# 05_Power.net
KiCad netlist of a schematic drawn in Altium Designer
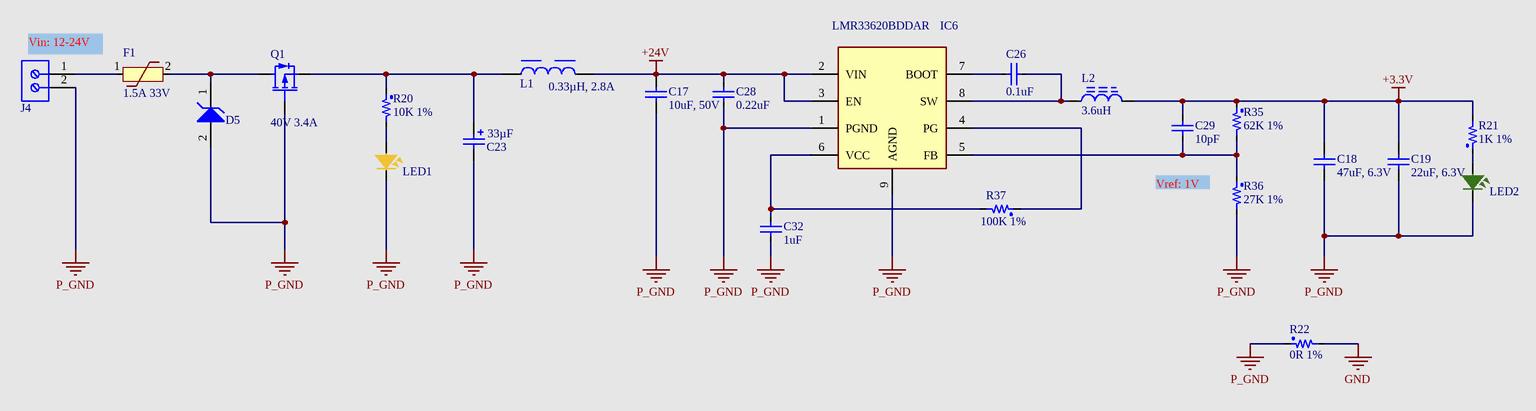
[diagram p0: 05_Power.SchDoc]

(export (version "E")
  (design (tool "Eeschema 10.0.6"))
  (components
    (comp (ref "C17")
      (value "10uF, 50V")
      (footprint "WCAP-CSGP_1210_H=2.5mm")
      (description "WCAP-CSGP Multilayer Ceramic Chip Capacitor, General Purpose, size 1210, X7R, 10uF, 50V")
      (fields (field (name "MFR PART NUMBER") "885012209073") (field (name "MFR") "Wurth Elektronik"))
      (libsource (lib "Altium_WCAP-CSGP (rev21a)") (part "885012209073"))
    )
    (comp (ref "C18")
      (value "47uF, 6.3V")
      (footprint "WCAP-CSGP_1206_H=1.6mm")
      (description "WCAP-CSGP Multilayer Ceramic Chip Capacitor, General Purpose, size 1206, X5R, 47uF, 6.3V")
      (fields (field (name "MFR PART NUMBER") "885012108004") (field (name "MFR") "Wurth Elektronik"))
      (libsource (lib "Altium_WCAP-CSGP (rev21a)") (part "885012108004"))
    )
    (comp (ref "C19")
      (value "22uF, 6.3V")
      (footprint "WCAP-CSGP_1206_H=1.6mm")
      (description "WCAP-CSGP Multilayer Ceramic Chip Capacitor, General Purpose, size 1206, X5R, 22uF, 6.3V")
      (fields (field (name "MFR PART NUMBER") "885012108003") (field (name "MFR") "Wurth Elektronik"))
      (libsource (lib "Altium_WCAP-CSGP (rev21a)") (part "885012108003"))
    )
    (comp (ref "C23")
      (value "33µF")
      (footprint "WCAP-PSLP_D5H5.8")
      (description "WCAP-PSLP Aluminum Polymer Capacitor, V-Chip SMT, D5 x H5.8mm, 33µF, 16V")
      (fields (field (name "MFR PART NUMBER") "875105359004") (field (name "MFR") "Wurth Elektronik"))
      (libsource (lib "Altium_WCAP-PSLP (rev22b)") (part "875105359004"))
    )
    (comp (ref "C26")
      (value "0.1uF")
      (footprint "Capacitor:C0603 (1608 metric)")
      (description "Multilayer Ceramic Capacitors MLCC - SMD/SMT 0.1uF 50V X7R +/-10% 0603")
      (fields (field (name "MFR PART NUMBER") "CC0603KRX7R9BB104") (field (name "MFR") "Yageo"))
      (libsource (lib "CeramicCapacitor") (part "CC0603KRX7R9BB104"))
    )
    (comp (ref "C28")
      (value "0.22uF")
      (footprint "Capacitor:C0805 (2012 METRIC)")
      (description "Multilayer Ceramic Capacitors MLCC - SMD/SMT 0805 50VDC 0.22uF 10% X7R")
      (fields (field (name "MFR PART NUMBER") "UMK212B7224KG-T") (field (name "MFR") "Taiyo Yuden"))
      (libsource (lib "CeramicCapacitor") (part "UMK212B7224KG-T"))
    )
    (comp (ref "C29")
      (value "10pF")
      (footprint "Capacitor:C0603 (1608 metric)")
      (description "Multilayer Ceramic Capacitors MLCC - SMD/SMT 10pF 250V C0G +/-5% 0603")
      (fields (field (name "MFR PART NUMBER") "CC0603JRNPO9BN100") (field (name "MFR") "Yageo"))
      (libsource (lib "CeramicCapacitor") (part "CC0603JRNPO9BN100"))
    )
    (comp (ref "C32")
      (value "1uF")
      (footprint "Capacitor:C0603 (1608 metric)")
      (description "Multilayer Ceramic Capacitors MLCC - SMD/SMT 1.0uF 16V X7R +/-10% 0603")
      (fields (field (name "MFR PART NUMBER") "CC0603KRX7R7BB105") (field (name "MFR") "Yageo"))
      (libsource (lib "CeramicCapacitor") (part "CC0603KRX7R7BB105"))
    )
    (comp (ref "D5")
      (value "400W, 26VDC")
      (footprint "WE-TVSP_DO-214AC_Unidirectional")
      (description "WE-TVSP SMT Power TVS Diode, DO-214AC, Unidirectional, 400W, 26VDC")
      (fields (field (name "MFR PART NUMBER") "824500261") (field (name "MFR") "Wurth Elektronik"))
      (libsource (lib "Altium_WE-TVSP (rev22b)") (part "824500261"))
    )
    (comp (ref "F1")
      (value "1.5A 33V")
      (footprint "FUSE_2902(7555 metric)")
      (description "Resettable Fuses - PPTC Fuse")
      (fields (field (name "MFR") "Bel Fuse") (field (name "MFR PART NUMBER") "0ZCF0150FF2C"))
      (libsource (lib "ResetableFuse") (part "0ZCF0150FF2C"))
    )
    (comp (ref "IC6")
      (value "LMR33620BDDAR")
      (footprint "SOIC127P600X170-9N")
      (description "Buck Switching Regulator IC Positive Adjustable 1V 1 Output 2A 8-PowerSOIC (0.154\", 3.90mm Width)")
      (fields (field (name "MFR") "Texas Instruments"))
      (libsource (lib "PowerManagement") (part "LMR33620BDDAR"))
    )
    (comp (ref "J4")
      (value "691103110002")
      (footprint "691103110002")
      (description "WR-TBL Series 1031 Horizontal Entry Modular, THT, pitch 3.5mm, 2p")
      (fields (field (name "MFR") "Wurth Elektronik"))
      (libsource (lib "Altium_WR-TBL (rev22b)") (part "691103110002"))
    )
    (comp (ref "L1")
      (value "0.33µH, 2.8A")
      (footprint "WE-TPC_2811")
      (description "WE-TPC SMT Tiny Power Inductor, 2811, 0.33µH, 2.8A, 35mΩ")
      (fields (field (name "MFR PART NUMBER") "74402800033") (field (name "MFR") "Wurth Elektronik"))
      (libsource (lib "WE-TPC (rev22c)") (part "74402800033"))
    )
    (comp (ref "L2")
      (value "3.6uH")
      (footprint "SRN80408R2Y")
      (description "Fixed Inductors 3.6uH 30% SMD 8040")
      (fields (field (name "MFR PART NUMBER") "SRN8040-3R6Y") (field (name "MFR") "Bourns"))
      (libsource (lib "Power Inductor") (part "SRN8040-3R6Y"))
    )
    (comp (ref "LED1")
      (value "Yellow")
      (footprint "LED:LED0603_YELLOW")
      (description "Standard LEDs - SMD 0603 Yellow Clear 588nm")
      (fields (field (name "MFR PART NUMBER") "LTST-C190YKT") (field (name "MFR") "Lite-On"))
      (libsource (lib "ChipLED") (part "LTST-C190YKT"))
    )
    (comp (ref "LED2")
      (value "Green")
      (footprint "LED:LED0603_GREEN")
      (description "Standard LEDs - SMD 0603 Green Clear 569nm")
      (fields (field (name "MFR PART NUMBER") "LTST-C191GKT") (field (name "MFR") "Lite-On"))
      (libsource (lib "ChipLED") (part "LTST-C191GKT"))
    )
    (comp (ref "Q1")
      (value "40V 3.4A")
      (footprint "FET_SOT23-3")
      (description "MOSFET MOSFET BVDSS: 31V-40V")
      (fields (field (name "MFR PART NUMBER") "DMP4065SQ-13") (field (name "MFR") "Diodes Incorporated"))
      (libsource (lib "MOSFET") (part "DMP4065SQ-13"))
    )
    (comp (ref "R20")
      (value "10K 1%")
      (footprint "Resistor:R0603 (1608 Metric)")
      (description "Thick Film Resistors - SMD 10K OHM 1% Case 0603")
      (fields (field (name "MFR PART NUMBER") "RC0603FR-0710KL") (field (name "MFR") "Yageo"))
      (libsource (lib "ChipResistor") (part "RC0603FR-0710KL"))
    )
    (comp (ref "R21")
      (value "1K 1%")
      (footprint "Resistor:R0603 (1608 Metric)")
      (description "Thick Film Resistors - SMD 1K OHM 1% Case 0603")
      (fields (field (name "MFR PART NUMBER") "RC0603FR-071KL") (field (name "MFR") "Yageo"))
      (libsource (lib "ChipResistor") (part "RC0603FR-071KL"))
    )
    (comp (ref "R22")
      (value "0R 1%")
      (footprint "Resistor:R0603 (1608 Metric)")
      (description "Thick Film Resistors - SMD 0 OHM 1% Case 0603")
      (fields (field (name "MFR PART NUMBER") "RC0603FR-070RL") (field (name "MFR") "Yageo"))
      (libsource (lib "ChipResistor") (part "RC0603FR-070RL"))
    )
    (comp (ref "R35")
      (value "62K 1%")
      (footprint "Resistor:R0603 (1608 Metric)")
      (description "Thick Film Resistors - SMD 62 kOhms 100mW 0603 1%")
      (fields (field (name "MFR PART NUMBER") "RC0603FR-0762KL") (field (name "MFR") "Yageo"))
      (libsource (lib "ChipResistor") (part "RC0603FR-0762KL"))
    )
    (comp (ref "R36")
      (value "27K 1%")
      (footprint "Resistor:R0603 (1608 Metric)")
      (description "Thick Film Resistors - SMD 27K OHM 1% Case 0603")
      (fields (field (name "MFR PART NUMBER") "RC0603FR-0727KL") (field (name "MFR") "Yageo"))
      (libsource (lib "ChipResistor") (part "RC0603FR-0727KL"))
    )
    (comp (ref "R37")
      (value "100K 1%")
      (footprint "Resistor:R0603 (1608 Metric)")
      (description "Thick Film Resistors - SMD 100K OHM 1% Case 0603")
      (fields (field (name "MFR PART NUMBER") "RC0603FR-07100KL") (field (name "MFR") "Yageo"))
      (libsource (lib "ChipResistor") (part "RC0603FR-07100KL"))
    )
  )
  (nets
    (net (code "1") (name "+3.3V") (class "Default")
      (node (ref "C18") (pin "2") (pinfunction "2_2") (pintype "passive"))
      (node (ref "C19") (pin "2") (pinfunction "2_2") (pintype "passive"))
      (node (ref "C29") (pin "2") (pinfunction "2_2") (pintype "passive"))
      (node (ref "L2") (pin "2") (pinfunction "2_2") (pintype "passive"))
      (node (ref "R21") (pin "2") (pinfunction "2_2") (pintype "passive"))
      (node (ref "R35") (pin "1") (pinfunction "1_1") (pintype "passive"))
    )
    (net (code "2") (name "+24V") (class "Default")
      (node (ref "C17") (pin "2") (pinfunction "2_2") (pintype "passive"))
      (node (ref "C28") (pin "1") (pinfunction "1_1") (pintype "passive"))
      (node (ref "IC6") (pin "2") (pinfunction "VIN_2") (pintype "passive"))
      (node (ref "IC6") (pin "3") (pinfunction "EN_3") (pintype "passive"))
      (node (ref "L1") (pin "2") (pinfunction "2_2") (pintype "passive"))
    )
    (net (code "3") (name "GND") (class "Default")
      (node (ref "R22") (pin "2") (pinfunction "2_2") (pintype "passive"))
    )
    (net (code "4") (name "Net-(C23-P)") (class "Default")
      (node (ref "C23") (pin "1") (pinfunction "P_1") (pintype "passive"))
      (node (ref "L1") (pin "1") (pinfunction "1_1") (pintype "passive"))
      (node (ref "Q1") (pin "2") (pinfunction "S_2") (pintype "passive"))
      (node (ref "R20") (pin "1") (pinfunction "1_1") (pintype "passive"))
    )
    (net (code "5") (name "Net-(D5-K)") (class "Default")
      (node (ref "D5") (pin "1") (pinfunction "K_1") (pintype "passive"))
      (node (ref "F1") (pin "2") (pinfunction "2_2") (pintype "passive"))
      (node (ref "Q1") (pin "3") (pinfunction "D_3") (pintype "passive"))
    )
    (net (code "6") (name "Net-(F1-Pad1)") (class "Default")
      (node (ref "F1") (pin "1") (pinfunction "1_1") (pintype "passive"))
      (node (ref "J4") (pin "1") (pinfunction "1_1") (pintype "passive"))
    )
    (net (code "7") (name "Net-(IC6-BOOT)") (class "Default")
      (node (ref "C26") (pin "1") (pinfunction "1_1") (pintype "passive"))
      (node (ref "IC6") (pin "7") (pinfunction "BOOT_7") (pintype "passive"))
    )
    (net (code "8") (name "Net-(IC6-FB)") (class "Default")
      (node (ref "C29") (pin "1") (pinfunction "1_1") (pintype "passive"))
      (node (ref "IC6") (pin "5") (pinfunction "FB_5") (pintype "passive"))
      (node (ref "R35") (pin "2") (pinfunction "2_2") (pintype "passive"))
      (node (ref "R36") (pin "1") (pinfunction "1_1") (pintype "passive"))
    )
    (net (code "9") (name "Net-(IC6-PG)") (class "Default")
      (node (ref "IC6") (pin "4") (pinfunction "PG_4") (pintype "passive"))
      (node (ref "R37") (pin "1") (pinfunction "1_1") (pintype "passive"))
    )
    (net (code "10") (name "Net-(IC6-SW)") (class "Default")
      (node (ref "C26") (pin "2") (pinfunction "2_2") (pintype "passive"))
      (node (ref "IC6") (pin "8") (pinfunction "SW_8") (pintype "passive"))
      (node (ref "L2") (pin "1") (pinfunction "1_1") (pintype "passive"))
    )
    (net (code "11") (name "Net-(IC6-VCC)") (class "Default")
      (node (ref "C32") (pin "2") (pinfunction "2_2") (pintype "passive"))
      (node (ref "IC6") (pin "6") (pinfunction "VCC_6") (pintype "passive"))
      (node (ref "R37") (pin "2") (pinfunction "2_2") (pintype "passive"))
    )
    (net (code "12") (name "Net-(LED1-Pad1)") (class "Default")
      (node (ref "LED1") (pin "1") (pinfunction "1_1") (pintype "passive"))
      (node (ref "R20") (pin "2") (pinfunction "2_2") (pintype "passive"))
    )
    (net (code "13") (name "Net-(LED2-Pad1)") (class "Default")
      (node (ref "LED2") (pin "1") (pinfunction "1_1") (pintype "passive"))
      (node (ref "R21") (pin "1") (pinfunction "1_1") (pintype "passive"))
    )
    (net (code "14") (name "P_GND") (class "Default")
      (node (ref "C17") (pin "1") (pinfunction "1_1") (pintype "passive"))
      (node (ref "C18") (pin "1") (pinfunction "1_1") (pintype "passive"))
      (node (ref "C19") (pin "1") (pinfunction "1_1") (pintype "passive"))
      (node (ref "C23") (pin "2") (pinfunction "N_2") (pintype "passive"))
      (node (ref "C28") (pin "2") (pinfunction "2_2") (pintype "passive"))
      (node (ref "C32") (pin "1") (pinfunction "1_1") (pintype "passive"))
      (node (ref "D5") (pin "2") (pinfunction "A_2") (pintype "passive"))
      (node (ref "IC6") (pin "1") (pinfunction "PGND_1") (pintype "passive"))
      (node (ref "IC6") (pin "9") (pinfunction "AGND_9") (pintype "passive"))
      (node (ref "J4") (pin "2") (pinfunction "2_2") (pintype "passive"))
      (node (ref "LED1") (pin "2") (pinfunction "2_2") (pintype "passive"))
      (node (ref "LED2") (pin "2") (pinfunction "2_2") (pintype "passive"))
      (node (ref "Q1") (pin "1") (pinfunction "G_1") (pintype "passive"))
      (node (ref "R22") (pin "1") (pinfunction "1_1") (pintype "passive"))
      (node (ref "R36") (pin "2") (pinfunction "2_2") (pintype "passive"))
    )
  )
)
